# TR_UBL_Splitter_V1p1.net
KiCad netlist of a schematic drawn in EAGLE
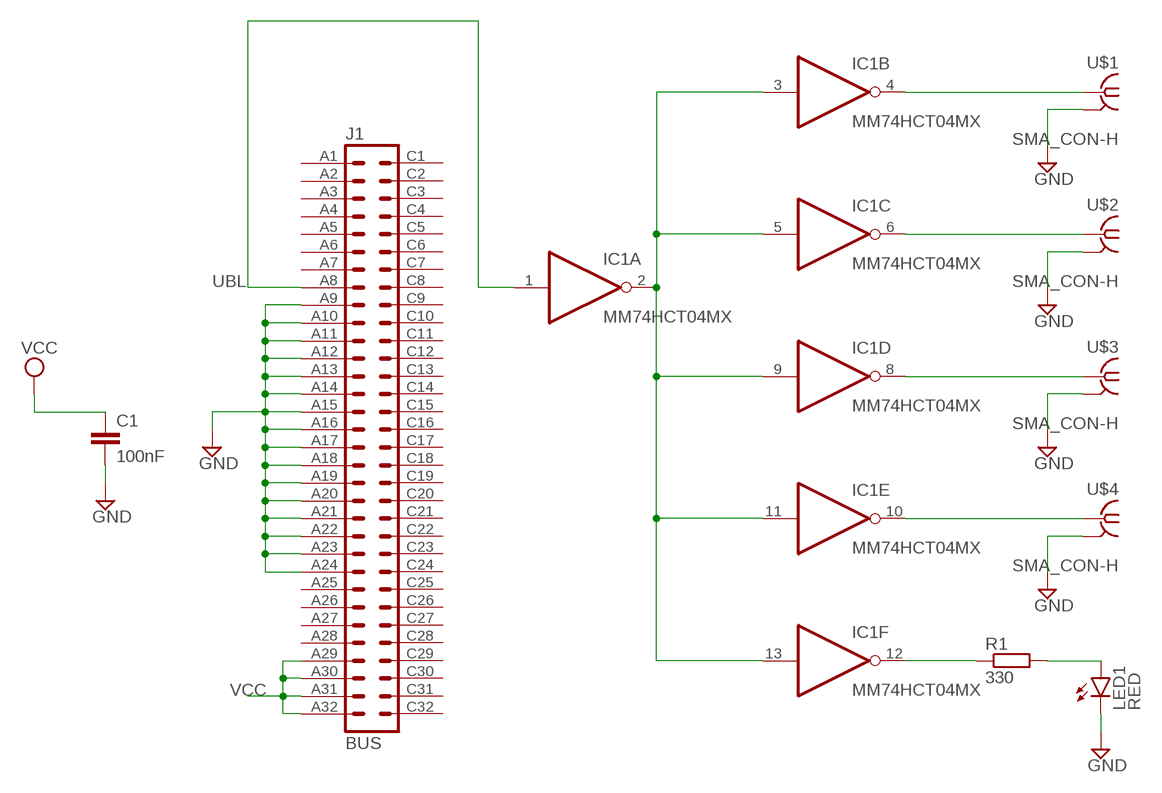
[diagram p0: schematic, sheet 1]

(export (version "E")
  (design (tool "Eeschema 10.0.6"))
  (components
    (comp (ref "C1")
      (value "100nF")
      (footprint "eagle-import:C0603")
      (libsource (lib "eagle-import") (part "C-EUC0603"))
    )
    (comp (ref "IC1")
      (value "MM74HCT04MX")
      (footprint "eagle-import:SO14")
      (libsource (lib "eagle-import") (part "7404D"))
    )
    (comp (ref "J1")
      (value "BUS")
      (footprint "eagle-import:VG64P")
      (libsource (lib "eagle-import") (part "VG64P"))
    )
    (comp (ref "LED1")
      (value "RED")
      (footprint "eagle-import:LED3MM")
      (libsource (lib "eagle-import") (part "LED3MM"))
    )
    (comp (ref "R1")
      (value "330")
      (footprint "eagle-import:R0603")
      (libsource (lib "eagle-import") (part "R-EU_R0603"))
    )
    (comp (ref "U$1")
      (value "SMA_CON-H")
      (footprint "eagle-import:BU-SMA-H")
      (libsource (lib "eagle-import") (part "SMA_CON-H"))
    )
    (comp (ref "U$2")
      (value "SMA_CON-H")
      (footprint "eagle-import:BU-SMA-H")
      (libsource (lib "eagle-import") (part "SMA_CON-H"))
    )
    (comp (ref "U$3")
      (value "SMA_CON-H")
      (footprint "eagle-import:BU-SMA-H")
      (libsource (lib "eagle-import") (part "SMA_CON-H"))
    )
    (comp (ref "U$4")
      (value "SMA_CON-H")
      (footprint "eagle-import:BU-SMA-H")
      (libsource (lib "eagle-import") (part "SMA_CON-H"))
    )
  )
  (nets
    (net (code "1") (name "GND") (class "Default")
      (node (ref "C1") (pin "2") (pinfunction "2_2") (pintype "passive"))
      (node (ref "J1") (pin "A10") (pinfunction "A10_A10") (pintype "passive"))
      (node (ref "J1") (pin "A11") (pinfunction "A11_A11") (pintype "passive"))
      (node (ref "J1") (pin "A12") (pinfunction "A12_A12") (pintype "passive"))
      (node (ref "J1") (pin "A13") (pinfunction "A13_A13") (pintype "passive"))
      (node (ref "J1") (pin "A14") (pinfunction "A14_A14") (pintype "passive"))
      (node (ref "J1") (pin "A15") (pinfunction "A15_A15") (pintype "passive"))
      (node (ref "J1") (pin "A16") (pinfunction "A16_A16") (pintype "passive"))
      (node (ref "J1") (pin "A17") (pinfunction "A17_A17") (pintype "passive"))
      (node (ref "J1") (pin "A18") (pinfunction "A18_A18") (pintype "passive"))
      (node (ref "J1") (pin "A19") (pinfunction "A19_A19") (pintype "passive"))
      (node (ref "J1") (pin "A20") (pinfunction "A20_A20") (pintype "passive"))
      (node (ref "J1") (pin "A21") (pinfunction "A21_A21") (pintype "passive"))
      (node (ref "J1") (pin "A22") (pinfunction "A22_A22") (pintype "passive"))
      (node (ref "J1") (pin "A23") (pinfunction "A23_A23") (pintype "passive"))
      (node (ref "J1") (pin "A24") (pinfunction "A24_A24") (pintype "passive"))
      (node (ref "J1") (pin "A9") (pinfunction "A9_A9") (pintype "passive"))
      (node (ref "LED1") (pin "K") (pinfunction "C_K") (pintype "passive"))
      (node (ref "U$1") (pin "2") (pinfunction "GND_2") (pintype "passive"))
      (node (ref "U$1") (pin "3") (pinfunction "GND_3") (pintype "passive"))
      (node (ref "U$1") (pin "4") (pinfunction "GND_4") (pintype "passive"))
      (node (ref "U$1") (pin "5") (pinfunction "GND_5") (pintype "passive"))
      (node (ref "U$2") (pin "2") (pinfunction "GND_2") (pintype "passive"))
      (node (ref "U$2") (pin "3") (pinfunction "GND_3") (pintype "passive"))
      (node (ref "U$2") (pin "4") (pinfunction "GND_4") (pintype "passive"))
      (node (ref "U$2") (pin "5") (pinfunction "GND_5") (pintype "passive"))
      (node (ref "U$3") (pin "2") (pinfunction "GND_2") (pintype "passive"))
      (node (ref "U$3") (pin "3") (pinfunction "GND_3") (pintype "passive"))
      (node (ref "U$3") (pin "4") (pinfunction "GND_4") (pintype "passive"))
      (node (ref "U$3") (pin "5") (pinfunction "GND_5") (pintype "passive"))
      (node (ref "U$4") (pin "2") (pinfunction "GND_2") (pintype "passive"))
      (node (ref "U$4") (pin "3") (pinfunction "GND_3") (pintype "passive"))
      (node (ref "U$4") (pin "4") (pinfunction "GND_4") (pintype "passive"))
      (node (ref "U$4") (pin "5") (pinfunction "GND_5") (pintype "passive"))
    )
    (net (code "2") (name "Net-(IC1A-O)") (class "Default")
      (node (ref "IC1") (pin "11") (pinfunction "I_11") (pintype "input"))
      (node (ref "IC1") (pin "13") (pinfunction "I_13") (pintype "input"))
      (node (ref "IC1") (pin "2") (pinfunction "O_2") (pintype "output"))
      (node (ref "IC1") (pin "3") (pinfunction "I_3") (pintype "input"))
      (node (ref "IC1") (pin "5") (pinfunction "I_5") (pintype "input"))
      (node (ref "IC1") (pin "9") (pinfunction "I_9") (pintype "input"))
    )
    (net (code "3") (name "Net-(IC1B-O)") (class "Default")
      (node (ref "IC1") (pin "4") (pinfunction "O_4") (pintype "output"))
      (node (ref "U$1") (pin "1") (pinfunction "1_1") (pintype "passive"))
    )
    (net (code "4") (name "Net-(IC1C-O)") (class "Default")
      (node (ref "IC1") (pin "6") (pinfunction "O_6") (pintype "output"))
      (node (ref "U$2") (pin "1") (pinfunction "1_1") (pintype "passive"))
    )
    (net (code "5") (name "Net-(IC1D-O)") (class "Default")
      (node (ref "IC1") (pin "8") (pinfunction "O_8") (pintype "output"))
      (node (ref "U$3") (pin "1") (pinfunction "1_1") (pintype "passive"))
    )
    (net (code "6") (name "Net-(IC1E-O)") (class "Default")
      (node (ref "IC1") (pin "10") (pinfunction "O_10") (pintype "output"))
      (node (ref "U$4") (pin "1") (pinfunction "1_1") (pintype "passive"))
    )
    (net (code "7") (name "Net-(IC1F-O)") (class "Default")
      (node (ref "IC1") (pin "12") (pinfunction "O_12") (pintype "output"))
      (node (ref "R1") (pin "1") (pinfunction "1_1") (pintype "passive"))
    )
    (net (code "8") (name "Net-(LED1-PadA)") (class "Default")
      (node (ref "LED1") (pin "A") (pinfunction "A_A") (pintype "passive"))
      (node (ref "R1") (pin "2") (pinfunction "2_2") (pintype "passive"))
    )
    (net (code "9") (name "UBL") (class "Default")
      (node (ref "IC1") (pin "1") (pinfunction "I_1") (pintype "input"))
      (node (ref "J1") (pin "A8") (pinfunction "A8_A8") (pintype "passive"))
    )
    (net (code "10") (name "VCC") (class "Default")
      (node (ref "C1") (pin "1") (pinfunction "1_1") (pintype "passive"))
      (node (ref "J1") (pin "A29") (pinfunction "A29_A29") (pintype "passive"))
      (node (ref "J1") (pin "A30") (pinfunction "A30_A30") (pintype "passive"))
      (node (ref "J1") (pin "A31") (pinfunction "A31_A31") (pintype "passive"))
      (node (ref "J1") (pin "A32") (pinfunction "A32_A32") (pintype "passive"))
    )
    (net (code "11") (name "unconnected-(J1-PadA1)") (class "Default")
      (node (ref "J1") (pin "A1") (pinfunction "A1_A1") (pintype "passive"))
    )
    (net (code "12") (name "unconnected-(J1-PadA2)") (class "Default")
      (node (ref "J1") (pin "A2") (pinfunction "A2_A2") (pintype "passive"))
    )
    (net (code "13") (name "unconnected-(J1-PadA3)") (class "Default")
      (node (ref "J1") (pin "A3") (pinfunction "A3_A3") (pintype "passive"))
    )
    (net (code "14") (name "unconnected-(J1-PadA4)") (class "Default")
      (node (ref "J1") (pin "A4") (pinfunction "A4_A4") (pintype "passive"))
    )
    (net (code "15") (name "unconnected-(J1-PadA5)") (class "Default")
      (node (ref "J1") (pin "A5") (pinfunction "A5_A5") (pintype "passive"))
    )
    (net (code "16") (name "unconnected-(J1-PadA6)") (class "Default")
      (node (ref "J1") (pin "A6") (pinfunction "A6_A6") (pintype "passive"))
    )
    (net (code "17") (name "unconnected-(J1-PadA7)") (class "Default")
      (node (ref "J1") (pin "A7") (pinfunction "A7_A7") (pintype "passive"))
    )
    (net (code "18") (name "unconnected-(J1-PadA25)") (class "Default")
      (node (ref "J1") (pin "A25") (pinfunction "A25_A25") (pintype "passive"))
    )
    (net (code "19") (name "unconnected-(J1-PadA26)") (class "Default")
      (node (ref "J1") (pin "A26") (pinfunction "A26_A26") (pintype "passive"))
    )
    (net (code "20") (name "unconnected-(J1-PadA27)") (class "Default")
      (node (ref "J1") (pin "A27") (pinfunction "A27_A27") (pintype "passive"))
    )
    (net (code "21") (name "unconnected-(J1-PadA28)") (class "Default")
      (node (ref "J1") (pin "A28") (pinfunction "A28_A28") (pintype "passive"))
    )
    (net (code "22") (name "unconnected-(J1-PadC1)") (class "Default")
      (node (ref "J1") (pin "C1") (pinfunction "C1_C1") (pintype "passive"))
    )
    (net (code "23") (name "unconnected-(J1-PadC2)") (class "Default")
      (node (ref "J1") (pin "C2") (pinfunction "C2_C2") (pintype "passive"))
    )
    (net (code "24") (name "unconnected-(J1-PadC3)") (class "Default")
      (node (ref "J1") (pin "C3") (pinfunction "C3_C3") (pintype "passive"))
    )
    (net (code "25") (name "unconnected-(J1-PadC4)") (class "Default")
      (node (ref "J1") (pin "C4") (pinfunction "C4_C4") (pintype "passive"))
    )
    (net (code "26") (name "unconnected-(J1-PadC5)") (class "Default")
      (node (ref "J1") (pin "C5") (pinfunction "C5_C5") (pintype "passive"))
    )
    (net (code "27") (name "unconnected-(J1-PadC6)") (class "Default")
      (node (ref "J1") (pin "C6") (pinfunction "C6_C6") (pintype "passive"))
    )
    (net (code "28") (name "unconnected-(J1-PadC7)") (class "Default")
      (node (ref "J1") (pin "C7") (pinfunction "C7_C7") (pintype "passive"))
    )
    (net (code "29") (name "unconnected-(J1-PadC8)") (class "Default")
      (node (ref "J1") (pin "C8") (pinfunction "C8_C8") (pintype "passive"))
    )
    (net (code "30") (name "unconnected-(J1-PadC9)") (class "Default")
      (node (ref "J1") (pin "C9") (pinfunction "C9_C9") (pintype "passive"))
    )
    (net (code "31") (name "unconnected-(J1-PadC10)") (class "Default")
      (node (ref "J1") (pin "C10") (pinfunction "C10_C10") (pintype "passive"))
    )
    (net (code "32") (name "unconnected-(J1-PadC11)") (class "Default")
      (node (ref "J1") (pin "C11") (pinfunction "C11_C11") (pintype "passive"))
    )
    (net (code "33") (name "unconnected-(J1-PadC12)") (class "Default")
      (node (ref "J1") (pin "C12") (pinfunction "C12_C12") (pintype "passive"))
    )
    (net (code "34") (name "unconnected-(J1-PadC13)") (class "Default")
      (node (ref "J1") (pin "C13") (pinfunction "C13_C13") (pintype "passive"))
    )
    (net (code "35") (name "unconnected-(J1-PadC14)") (class "Default")
      (node (ref "J1") (pin "C14") (pinfunction "C14_C14") (pintype "passive"))
    )
    (net (code "36") (name "unconnected-(J1-PadC15)") (class "Default")
      (node (ref "J1") (pin "C15") (pinfunction "C15_C15") (pintype "passive"))
    )
    (net (code "37") (name "unconnected-(J1-PadC16)") (class "Default")
      (node (ref "J1") (pin "C16") (pinfunction "C16_C16") (pintype "passive"))
    )
    (net (code "38") (name "unconnected-(J1-PadC17)") (class "Default")
      (node (ref "J1") (pin "C17") (pinfunction "C17_C17") (pintype "passive"))
    )
    (net (code "39") (name "unconnected-(J1-PadC18)") (class "Default")
      (node (ref "J1") (pin "C18") (pinfunction "C18_C18") (pintype "passive"))
    )
    (net (code "40") (name "unconnected-(J1-PadC19)") (class "Default")
      (node (ref "J1") (pin "C19") (pinfunction "C19_C19") (pintype "passive"))
    )
    (net (code "41") (name "unconnected-(J1-PadC20)") (class "Default")
      (node (ref "J1") (pin "C20") (pinfunction "C20_C20") (pintype "passive"))
    )
    (net (code "42") (name "unconnected-(J1-PadC21)") (class "Default")
      (node (ref "J1") (pin "C21") (pinfunction "C21_C21") (pintype "passive"))
    )
    (net (code "43") (name "unconnected-(J1-PadC22)") (class "Default")
      (node (ref "J1") (pin "C22") (pinfunction "C22_C22") (pintype "passive"))
    )
    (net (code "44") (name "unconnected-(J1-PadC23)") (class "Default")
      (node (ref "J1") (pin "C23") (pinfunction "C23_C23") (pintype "passive"))
    )
    (net (code "45") (name "unconnected-(J1-PadC24)") (class "Default")
      (node (ref "J1") (pin "C24") (pinfunction "C24_C24") (pintype "passive"))
    )
    (net (code "46") (name "unconnected-(J1-PadC25)") (class "Default")
      (node (ref "J1") (pin "C25") (pinfunction "C25_C25") (pintype "passive"))
    )
    (net (code "47") (name "unconnected-(J1-PadC26)") (class "Default")
      (node (ref "J1") (pin "C26") (pinfunction "C26_C26") (pintype "passive"))
    )
    (net (code "48") (name "unconnected-(J1-PadC27)") (class "Default")
      (node (ref "J1") (pin "C27") (pinfunction "C27_C27") (pintype "passive"))
    )
    (net (code "49") (name "unconnected-(J1-PadC28)") (class "Default")
      (node (ref "J1") (pin "C28") (pinfunction "C28_C28") (pintype "passive"))
    )
    (net (code "50") (name "unconnected-(J1-PadC29)") (class "Default")
      (node (ref "J1") (pin "C29") (pinfunction "C29_C29") (pintype "passive"))
    )
    (net (code "51") (name "unconnected-(J1-PadC30)") (class "Default")
      (node (ref "J1") (pin "C30") (pinfunction "C30_C30") (pintype "passive"))
    )
    (net (code "52") (name "unconnected-(J1-PadC31)") (class "Default")
      (node (ref "J1") (pin "C31") (pinfunction "C31_C31") (pintype "passive"))
    )
    (net (code "53") (name "unconnected-(J1-PadC32)") (class "Default")
      (node (ref "J1") (pin "C32") (pinfunction "C32_C32") (pintype "passive"))
    )
  )
)
